# Power_1.net
KiCad netlist of a schematic drawn in Altium Designer
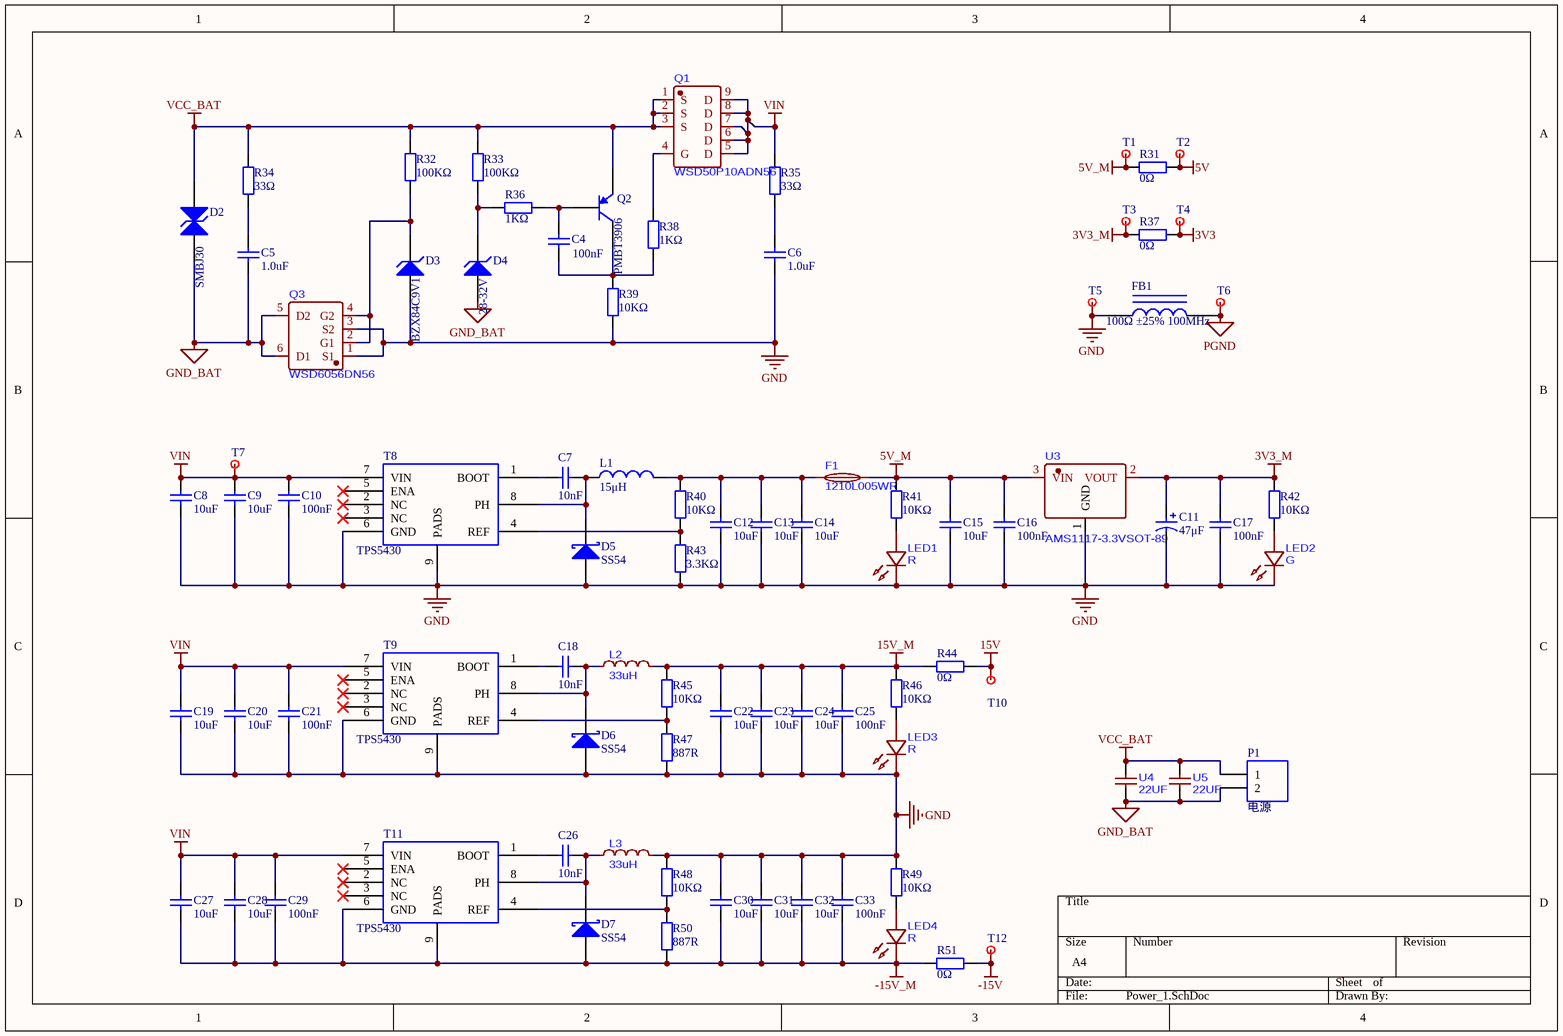
[diagram p0: Power_1.SchDoc]

(export (version "E")
  (design (tool "Eeschema 10.0.6"))
  (components
    (comp (ref "C4")
      (value "100nF")
      (footprint "0402_C")
      (description "贴片电容")
      (libsource (lib "Miscellaneous Devices LC") (part "0402 100nF (104) 10% 16V"))
    )
    (comp (ref "C5")
      (value "1.0uF")
      (footprint "0402_C")
      (description "贴片电容")
      (libsource (lib "Miscellaneous Devices LC") (part "0402 1.0uF (105) 10% 25V"))
    )
    (comp (ref "C6")
      (value "1.0uF")
      (footprint "0402_C")
      (description "贴片电容")
      (libsource (lib "Miscellaneous Devices LC") (part "0402 1.0uF (105) 10% 25V"))
    )
    (comp (ref "C7")
      (value "10nF")
      (footprint "0402_C")
      (description "贴片电容")
      (libsource (lib "Miscellaneous Devices LC") (part "0402 10nF (103) 10% 50V"))
    )
    (comp (ref "C8")
      (value "10uF")
      (footprint "1206_C")
      (description "贴片电容")
      (libsource (lib "Miscellaneous Devices LC") (part "1206 10uF (106) 10% 50V"))
    )
    (comp (ref "C9")
      (value "10uF")
      (footprint "1206_C")
      (description "贴片电容")
      (libsource (lib "Miscellaneous Devices LC") (part "1206 10uF (106) 10% 50V"))
    )
    (comp (ref "C10")
      (value "100nF")
      (footprint "0603_C")
      (description "贴片电容")
      (libsource (lib "Miscellaneous Devices LC") (part "0603 100nF (104) 10% 50V"))
    )
    (comp (ref "C11")
      (value "47μF")
      (footprint "钽电容47")
      (description "钽电容")
      (fields (field (name "PUBLISHER") "Altium Limited"))
      (libsource (lib "RM2020原理图库v1.3 (1)") (part "47μF"))
    )
    (comp (ref "C12")
      (value "10uF")
      (footprint "1206_C")
      (description "贴片电容")
      (libsource (lib "Miscellaneous Devices LC") (part "1206 10uF (106) 10% 50V"))
    )
    (comp (ref "C13")
      (value "10uF")
      (footprint "1206_C")
      (description "贴片电容")
      (libsource (lib "Miscellaneous Devices LC") (part "1206 10uF (106) 10% 50V"))
    )
    (comp (ref "C14")
      (value "10uF")
      (footprint "1206_C")
      (description "贴片电容")
      (libsource (lib "Miscellaneous Devices LC") (part "1206 10uF (106) 10% 50V"))
    )
    (comp (ref "C15")
      (value "10uF")
      (footprint "0603_C")
      (description "贴片电容")
      (libsource (lib "Miscellaneous Devices LC") (part "0603 100nF (104) 10% 50V"))
    )
    (comp (ref "C16")
      (value "100nF")
      (footprint "0603_C")
      (description "贴片电容")
      (libsource (lib "Miscellaneous Devices LC") (part "0603 100nF (104) 10% 50V"))
    )
    (comp (ref "C17")
      (value "100nF")
      (footprint "0603_C")
      (description "贴片电容")
      (libsource (lib "Miscellaneous Devices LC") (part "0603 100nF (104) 10% 50V"))
    )
    (comp (ref "C18")
      (value "10nF")
      (footprint "0402_C")
      (description "贴片电容")
      (libsource (lib "Miscellaneous Devices LC") (part "0402 10nF (103) 10% 50V"))
    )
    (comp (ref "C19")
      (value "10uF")
      (footprint "1206_C")
      (description "贴片电容")
      (libsource (lib "Miscellaneous Devices LC") (part "1206 10uF (106) 10% 50V"))
    )
    (comp (ref "C20")
      (value "10uF")
      (footprint "1206_C")
      (description "贴片电容")
      (libsource (lib "Miscellaneous Devices LC") (part "1206 10uF (106) 10% 50V"))
    )
    (comp (ref "C21")
      (value "100nF")
      (footprint "0603_C")
      (description "贴片电容")
      (libsource (lib "Miscellaneous Devices LC") (part "0603 100nF (104) 10% 50V"))
    )
    (comp (ref "C22")
      (value "10uF")
      (footprint "1206_C")
      (description "贴片电容")
      (libsource (lib "Miscellaneous Devices LC") (part "1206 10uF (106) 10% 50V"))
    )
    (comp (ref "C23")
      (value "10uF")
      (footprint "1206_C")
      (description "贴片电容")
      (libsource (lib "Miscellaneous Devices LC") (part "1206 10uF (106) 10% 50V"))
    )
    (comp (ref "C24")
      (value "10uF")
      (footprint "1206_C")
      (description "贴片电容")
      (libsource (lib "Miscellaneous Devices LC") (part "1206 10uF (106) 10% 50V"))
    )
    (comp (ref "C25")
      (value "100nF")
      (footprint "0603_C")
      (description "贴片电容")
      (libsource (lib "Miscellaneous Devices LC") (part "0603 100nF (104) 10% 50V"))
    )
    (comp (ref "C26")
      (value "10nF")
      (footprint "0402_C")
      (description "贴片电容")
      (libsource (lib "Miscellaneous Devices LC") (part "0402 10nF (103) 10% 50V"))
    )
    (comp (ref "C27")
      (value "10uF")
      (footprint "1206_C")
      (description "贴片电容")
      (libsource (lib "Miscellaneous Devices LC") (part "1206 10uF (106) 10% 50V"))
    )
    (comp (ref "C28")
      (value "10uF")
      (footprint "1206_C")
      (description "贴片电容")
      (libsource (lib "Miscellaneous Devices LC") (part "1206 10uF (106) 10% 50V"))
    )
    (comp (ref "C29")
      (value "100nF")
      (footprint "0603_C")
      (description "贴片电容")
      (libsource (lib "Miscellaneous Devices LC") (part "0603 100nF (104) 10% 50V"))
    )
    (comp (ref "C30")
      (value "10uF")
      (footprint "1206_C")
      (description "贴片电容")
      (libsource (lib "Miscellaneous Devices LC") (part "1206 10uF (106) 10% 50V"))
    )
    (comp (ref "C31")
      (value "10uF")
      (footprint "1206_C")
      (description "贴片电容")
      (libsource (lib "Miscellaneous Devices LC") (part "1206 10uF (106) 10% 50V"))
    )
    (comp (ref "C32")
      (value "10uF")
      (footprint "1206_C")
      (description "贴片电容")
      (libsource (lib "Miscellaneous Devices LC") (part "1206 10uF (106) 10% 50V"))
    )
    (comp (ref "C33")
      (value "100nF")
      (footprint "0603_C")
      (description "贴片电容")
      (libsource (lib "Miscellaneous Devices LC") (part "0603 100nF (104) 10% 50V"))
    )
    (comp (ref "D2")
      (value "SMBJ30")
      (footprint "SMB(DO-214AA)_S1")
      (description "TVS")
      (libsource (lib "Miscellaneous Devices LC") (part "SMB/DO-214AA P6SMB6.8CA"))
    )
    (comp (ref "D3")
      (value "BZX84C9V1")
      (footprint "SOD-123")
      (description "稳压二极管")
      (libsource (lib "RM2020原理图库v1.3 (1)") (part "稳压二极管"))
    )
    (comp (ref "D4")
      (value "28-32V")
      (footprint "SOD-123")
      (description "稳压二极管")
      (libsource (lib "RM2020原理图库v1.3 (1)") (part "稳压二极管"))
    )
    (comp (ref "D5")
      (value "SS54")
      (footprint "SS54")
      (description "Schottky Diode")
      (fields (field (name "PUBLISHER") "Altium Limited"))
      (libsource (lib "RM2020原理图库v1.3 (1)") (part "SS54"))
    )
    (comp (ref "D6")
      (value "SS54")
      (footprint "SS54")
      (description "Schottky Diode")
      (fields (field (name "PUBLISHER") "Altium Limited"))
      (libsource (lib "RM2020原理图库v1.3 (1)") (part "SS54"))
    )
    (comp (ref "D7")
      (value "SS54")
      (footprint "SS54")
      (description "Schottky Diode")
      (fields (field (name "PUBLISHER") "Altium Limited"))
      (libsource (lib "RM2020原理图库v1.3 (1)") (part "SS54"))
    )
    (comp (ref "F1") (value "1210L005WR") (footprint "F1210") (libsource (lib "JiangCi") (part "1210L005WR")))
    (comp (ref "FB1")
      (value "100Ω ±25% 100MHz")
      (footprint "0805_L")
      (description "贴片磁珠")
      (libsource (lib "Miscellaneous Devices LC") (part "0805 100Ω 25% 100MHz"))
    )
    (comp (ref "L1")
      (value "15μH")
      (footprint "电感")
      (description "贴片电感")
      (fields (field (name "PUBLISHER") "Altium Limited"))
      (libsource (lib "RM2020原理图库v1.3 (1)") (part "15μH"))
    )
    (comp (ref "L2")
      (value "33uH")
      (footprint "IND-SMD_L5.5-W5.0")
      (libsource (lib "JiangCi") (part "YXMAC0502-3R3M-ANF"))
    )
    (comp (ref "L3")
      (value "33uH")
      (footprint "IND-SMD_L5.5-W5.0")
      (libsource (lib "JiangCi") (part "YXMAC0502-3R3M-ANF"))
    )
    (comp (ref "LED1")
      (value "R")
      (footprint "LED0402-RD")
      (libsource (lib "JiangCi") (part "TJ-S1005CL4T5ALC3DW-A5"))
    )
    (comp (ref "LED2")
      (value "G")
      (footprint "LED0402-RD")
      (libsource (lib "JiangCi") (part "TJ-S1005CL4T5ALC3DW-A5"))
    )
    (comp (ref "LED3")
      (value "R")
      (footprint "LED0402-RD")
      (libsource (lib "JiangCi") (part "TJ-S1005CL4T5ALC3DW-A5"))
    )
    (comp (ref "LED4")
      (value "R")
      (footprint "LED0402-RD")
      (libsource (lib "JiangCi") (part "TJ-S1005CL4T5ALC3DW-A5"))
    )
    (comp (ref "P1")
      (value "电源")
      (footprint "XT30U公头")
      (description "Header, 2-Pin")
      (fields (field (name "PUBLISHER") "Altium Limited"))
      (libsource (lib "RM2020原理图库v1.3 (1)") (part "XT30公头立式"))
    )
    (comp (ref "Q1")
      (value "WSD50P10ADN56")
      (footprint "DFN-8_L5.8-W4.9-P1.27-LS6.0-BL-1")
      (libsource (lib "VeryNB_H750") (part "WSD50P10ADN56"))
    )
    (comp (ref "Q2")
      (value "PMBT3906")
      (footprint "SOT-23")
      (description "三极管")
      (libsource (lib "RM2020原理图库v1.3 (1)") (part "PNP三极管"))
    )
    (comp (ref "Q3")
      (value "WSD6056DN56")
      (footprint "DFN-8_L5.5-W5.2-P1.27-LS6.0-BL-EP2")
      (libsource (lib "VeryNB_H750") (part "WSD6056DN56"))
    )
    (comp (ref "R31")
      (value "0Ω")
      (footprint "0603_R")
      (description "贴片电阻")
      (libsource (lib "Miscellaneous Devices LC") (part "0603 0Ω (0R0) 1%"))
    )
    (comp (ref "R32")
      (value "100KΩ")
      (footprint "0402_R")
      (description "贴片电阻")
      (libsource (lib "Miscellaneous Devices LC") (part "0402 100KΩ (1003) 1%"))
    )
    (comp (ref "R33")
      (value "100KΩ")
      (footprint "0402_R")
      (description "贴片电阻")
      (libsource (lib "Miscellaneous Devices LC") (part "0402 100KΩ (1003) 1%"))
    )
    (comp (ref "R34")
      (value "33Ω")
      (footprint "0402_R")
      (description "贴片电阻")
      (libsource (lib "Miscellaneous Devices LC") (part "0402 33Ω (33R0) 1%"))
    )
    (comp (ref "R35")
      (value "33Ω")
      (footprint "0402_R")
      (description "贴片电阻")
      (libsource (lib "Miscellaneous Devices LC") (part "0402 33Ω (33R0) 1%"))
    )
    (comp (ref "R36")
      (value "1KΩ")
      (footprint "0402_R")
      (description "贴片电阻")
      (libsource (lib "") (part "0402 1KΩ (1001) 1%_1"))
    )
    (comp (ref "R37")
      (value "0Ω")
      (footprint "0603_R")
      (description "贴片电阻")
      (libsource (lib "Miscellaneous Devices LC") (part "0603 0Ω (0R0) 1%"))
    )
    (comp (ref "R38")
      (value "1KΩ")
      (footprint "0402_R")
      (description "贴片电阻")
      (libsource (lib "Miscellaneous Devices LC") (part "0402 1KΩ (1001) 1%"))
    )
    (comp (ref "R39")
      (value "10KΩ")
      (footprint "0402_R")
      (description "贴片电阻")
      (libsource (lib "") (part "0402 10KΩ (1002) 1%_1"))
    )
    (comp (ref "R40")
      (value "10KΩ")
      (footprint "0402_R")
      (description "贴片电阻")
      (libsource (lib "Miscellaneous Devices LC") (part "0402 10KΩ (1002) 1%"))
    )
    (comp (ref "R41")
      (value "10KΩ")
      (footprint "0402_R")
      (description "贴片电阻")
      (libsource (lib "Miscellaneous Devices LC") (part "0402 10KΩ (1002) 1%"))
    )
    (comp (ref "R42")
      (value "10KΩ")
      (footprint "0402_R")
      (description "贴片电阻")
      (libsource (lib "Miscellaneous Devices LC") (part "0402 10KΩ (1002) 1%"))
    )
    (comp (ref "R43")
      (value "3.3KΩ")
      (footprint "0402_R")
      (description "贴片电阻")
      (libsource (lib "Miscellaneous Devices LC") (part "0402 3.3KΩ (3301) 1%"))
    )
    (comp (ref "R44")
      (value "0Ω")
      (footprint "0603_R")
      (description "贴片电阻")
      (libsource (lib "Miscellaneous Devices LC") (part "0603 0Ω (0R0) 1%"))
    )
    (comp (ref "R45")
      (value "10KΩ")
      (footprint "0402_R")
      (description "贴片电阻")
      (libsource (lib "Miscellaneous Devices LC") (part "0402 10KΩ (1002) 1%"))
    )
    (comp (ref "R46")
      (value "10KΩ")
      (footprint "0402_R")
      (description "贴片电阻")
      (libsource (lib "Miscellaneous Devices LC") (part "0402 10KΩ (1002) 1%"))
    )
    (comp (ref "R47")
      (value "887R")
      (footprint "0402_R")
      (description "贴片电阻")
      (libsource (lib "Miscellaneous Devices LC") (part "0402 3.3KΩ (3301) 1%"))
    )
    (comp (ref "R48")
      (value "10KΩ")
      (footprint "0402_R")
      (description "贴片电阻")
      (libsource (lib "Miscellaneous Devices LC") (part "0402 10KΩ (1002) 1%"))
    )
    (comp (ref "R49")
      (value "10KΩ")
      (footprint "0402_R")
      (description "贴片电阻")
      (libsource (lib "Miscellaneous Devices LC") (part "0402 10KΩ (1002) 1%"))
    )
    (comp (ref "R50")
      (value "887R")
      (footprint "0402_R")
      (description "贴片电阻")
      (libsource (lib "Miscellaneous Devices LC") (part "0402 3.3KΩ (3301) 1%"))
    )
    (comp (ref "R51")
      (value "0Ω")
      (footprint "0603_R")
      (description "贴片电阻")
      (libsource (lib "Miscellaneous Devices LC") (part "0603 0Ω (0R0) 1%"))
    )
    (comp (ref "T1")
      (value "testpoint")
      (footprint "testpoint")
      (libsource (lib "JiangCi") (part "testpoint"))
    )
    (comp (ref "T2")
      (value "testpoint")
      (footprint "testpoint")
      (libsource (lib "JiangCi") (part "testpoint"))
    )
    (comp (ref "T3")
      (value "testpoint")
      (footprint "testpoint")
      (libsource (lib "JiangCi") (part "testpoint"))
    )
    (comp (ref "T4")
      (value "testpoint")
      (footprint "testpoint")
      (libsource (lib "JiangCi") (part "testpoint"))
    )
    (comp (ref "T5")
      (value "testpoint")
      (footprint "testpoint")
      (libsource (lib "JiangCi") (part "testpoint"))
    )
    (comp (ref "T6")
      (value "testpoint")
      (footprint "testpoint")
      (libsource (lib "JiangCi") (part "testpoint"))
    )
    (comp (ref "T7")
      (value "testpoint")
      (footprint "testpoint")
      (libsource (lib "JiangCi") (part "testpoint"))
    )
    (comp (ref "T8")
      (value "TPS5430")
      (footprint "TPS5430DDAR")
      (description "24V-5V")
      (libsource (lib "RM2020原理图库v1.3 (1)") (part "TPS5430"))
    )
    (comp (ref "T9")
      (value "TPS5430")
      (footprint "TPS5430DDAR")
      (description "24V-5V")
      (libsource (lib "RM2020原理图库v1.3 (1)") (part "TPS5430"))
    )
    (comp (ref "T10")
      (value "testpoint")
      (footprint "testpoint")
      (libsource (lib "JiangCi") (part "testpoint"))
    )
    (comp (ref "T11")
      (value "TPS5430")
      (footprint "TPS5430DDAR")
      (description "24V-5V")
      (libsource (lib "RM2020原理图库v1.3 (1)") (part "TPS5430"))
    )
    (comp (ref "T12")
      (value "testpoint")
      (footprint "testpoint")
      (libsource (lib "JiangCi") (part "testpoint"))
    )
    (comp (ref "U3")
      (value "AMS1117-3.3VSOT-89")
      (footprint "SOT-89-3_L4.5-W2.5-P1.50-LS4.2-BR")
      (libsource (lib "JiangCi") (part "AMS1117-3.3VSOT-89"))
    )
    (comp (ref "U4")
      (value "22UF")
      (footprint "C1812")
      (libsource (lib "VeryNB_H750") (part "100UF/50V-1812"))
    )
    (comp (ref "U5")
      (value "22UF")
      (footprint "C1812")
      (libsource (lib "VeryNB_H750") (part "100UF/50V-1812"))
    )
  )
  (nets
    (net (code "1") (name "-15V") (class "Default")
      (node (ref "R51") (pin "2") (pinfunction "2_2") (pintype "passive"))
      (node (ref "T12") (pin "1") (pinfunction "R_1") (pintype "passive"))
    )
    (net (code "2") (name "-15V_M") (class "Default")
      (node (ref "C27") (pin "1") (pinfunction "1_1") (pintype "passive"))
      (node (ref "C28") (pin "1") (pinfunction "1_1") (pintype "passive"))
      (node (ref "C29") (pin "1") (pinfunction "1_1") (pintype "passive"))
      (node (ref "C30") (pin "1") (pinfunction "1_1") (pintype "passive"))
      (node (ref "C31") (pin "1") (pinfunction "1_1") (pintype "passive"))
      (node (ref "C32") (pin "1") (pinfunction "1_1") (pintype "passive"))
      (node (ref "C33") (pin "1") (pinfunction "1_1") (pintype "passive"))
      (node (ref "D7") (pin "1") (pinfunction "A_1") (pintype "passive"))
      (node (ref "LED4") (pin "1") (pinfunction "K_1") (pintype "passive"))
      (node (ref "R50") (pin "1") (pinfunction "1_1") (pintype "passive"))
      (node (ref "R51") (pin "1") (pinfunction "1_1") (pintype "passive"))
      (node (ref "T11") (pin "6") (pinfunction "GND_6") (pintype "passive"))
      (node (ref "T11") (pin "9") (pinfunction "PADS_9") (pintype "passive"))
    )
    (net (code "3") (name "3V3") (class "Default")
      (node (ref "R37") (pin "2") (pinfunction "2_2") (pintype "passive"))
      (node (ref "T4") (pin "1") (pinfunction "R_1") (pintype "passive"))
    )
    (net (code "4") (name "3V3_M") (class "Default")
      (node (ref "C11") (pin "1") (pinfunction "1_1") (pintype "passive"))
      (node (ref "C17") (pin "2") (pinfunction "2_2") (pintype "passive"))
      (node (ref "R37") (pin "1") (pinfunction "1_1") (pintype "passive"))
      (node (ref "R42") (pin "2") (pinfunction "2_2") (pintype "passive"))
      (node (ref "T3") (pin "1") (pinfunction "R_1") (pintype "passive"))
      (node (ref "U3") (pin "2") (pinfunction "VOUT_2") (pintype "passive"))
    )
    (net (code "5") (name "5V") (class "Default")
      (node (ref "R31") (pin "2") (pinfunction "2_2") (pintype "passive"))
      (node (ref "T2") (pin "1") (pinfunction "R_1") (pintype "passive"))
    )
    (net (code "6") (name "5V_M") (class "Default")
      (node (ref "C15") (pin "2") (pinfunction "2_2") (pintype "passive"))
      (node (ref "C16") (pin "2") (pinfunction "2_2") (pintype "passive"))
      (node (ref "F1") (pin "2") (pinfunction "2_2") (pintype "passive"))
      (node (ref "R31") (pin "1") (pinfunction "1_1") (pintype "passive"))
      (node (ref "R41") (pin "2") (pinfunction "2_2") (pintype "passive"))
      (node (ref "T1") (pin "1") (pinfunction "R_1") (pintype "passive"))
      (node (ref "U3") (pin "3") (pinfunction "VIN_3") (pintype "passive"))
    )
    (net (code "7") (name "15V") (class "Default")
      (node (ref "R44") (pin "2") (pinfunction "2_2") (pintype "passive"))
      (node (ref "T10") (pin "1") (pinfunction "R_1") (pintype "passive"))
    )
    (net (code "8") (name "15V_M") (class "Default")
      (node (ref "C22") (pin "2") (pinfunction "2_2") (pintype "passive"))
      (node (ref "C23") (pin "2") (pinfunction "2_2") (pintype "passive"))
      (node (ref "C24") (pin "2") (pinfunction "2_2") (pintype "passive"))
      (node (ref "C25") (pin "2") (pinfunction "2_2") (pintype "passive"))
      (node (ref "L2") (pin "2") (pinfunction "2_2") (pintype "passive"))
      (node (ref "R44") (pin "1") (pinfunction "1_1") (pintype "passive"))
      (node (ref "R45") (pin "2") (pinfunction "2_2") (pintype "passive"))
      (node (ref "R46") (pin "2") (pinfunction "2_2") (pintype "passive"))
    )
    (net (code "9") (name "GND") (class "Default")
      (node (ref "C10") (pin "1") (pinfunction "1_1") (pintype "passive"))
      (node (ref "C11") (pin "2") (pinfunction "2_2") (pintype "passive"))
      (node (ref "C12") (pin "1") (pinfunction "1_1") (pintype "passive"))
      (node (ref "C13") (pin "1") (pinfunction "1_1") (pintype "passive"))
      (node (ref "C14") (pin "1") (pinfunction "1_1") (pintype "passive"))
      (node (ref "C15") (pin "1") (pinfunction "1_1") (pintype "passive"))
      (node (ref "C16") (pin "1") (pinfunction "1_1") (pintype "passive"))
      (node (ref "C17") (pin "1") (pinfunction "1_1") (pintype "passive"))
      (node (ref "C19") (pin "1") (pinfunction "1_1") (pintype "passive"))
      (node (ref "C20") (pin "1") (pinfunction "1_1") (pintype "passive"))
      (node (ref "C21") (pin "1") (pinfunction "1_1") (pintype "passive"))
      (node (ref "C22") (pin "1") (pinfunction "1_1") (pintype "passive"))
      (node (ref "C23") (pin "1") (pinfunction "1_1") (pintype "passive"))
      (node (ref "C24") (pin "1") (pinfunction "1_1") (pintype "passive"))
      (node (ref "C25") (pin "1") (pinfunction "1_1") (pintype "passive"))
      (node (ref "C30") (pin "2") (pinfunction "2_2") (pintype "passive"))
      (node (ref "C31") (pin "2") (pinfunction "2_2") (pintype "passive"))
      (node (ref "C32") (pin "2") (pinfunction "2_2") (pintype "passive"))
      (node (ref "C33") (pin "2") (pinfunction "2_2") (pintype "passive"))
      (node (ref "C6") (pin "1") (pinfunction "1_1") (pintype "passive"))
      (node (ref "C8") (pin "1") (pinfunction "1_1") (pintype "passive"))
      (node (ref "C9") (pin "1") (pinfunction "1_1") (pintype "passive"))
      (node (ref "D3") (pin "1") (pinfunction "A_1") (pintype "passive"))
      (node (ref "D5") (pin "1") (pinfunction "A_1") (pintype "passive"))
      (node (ref "D6") (pin "1") (pinfunction "A_1") (pintype "passive"))
      (node (ref "FB1") (pin "1") (pinfunction "1_1") (pintype "passive"))
      (node (ref "L3") (pin "2") (pinfunction "2_2") (pintype "passive"))
      (node (ref "LED1") (pin "1") (pinfunction "K_1") (pintype "passive"))
      (node (ref "LED2") (pin "1") (pinfunction "K_1") (pintype "passive"))
      (node (ref "LED3") (pin "1") (pinfunction "K_1") (pintype "passive"))
      (node (ref "Q3") (pin "1") (pinfunction "S1_1") (pintype "passive"))
      (node (ref "Q3") (pin "3") (pinfunction "S2_3") (pintype "passive"))
      (node (ref "R39") (pin "2") (pinfunction "2_2") (pintype "passive"))
      (node (ref "R43") (pin "1") (pinfunction "1_1") (pintype "passive"))
      (node (ref "R47") (pin "1") (pinfunction "1_1") (pintype "passive"))
      (node (ref "R48") (pin "2") (pinfunction "2_2") (pintype "passive"))
      (node (ref "R49") (pin "2") (pinfunction "2_2") (pintype "passive"))
      (node (ref "T5") (pin "1") (pinfunction "R_1") (pintype "passive"))
      (node (ref "T8") (pin "6") (pinfunction "GND_6") (pintype "passive"))
      (node (ref "T8") (pin "9") (pinfunction "PADS_9") (pintype "passive"))
      (node (ref "T9") (pin "6") (pinfunction "GND_6") (pintype "passive"))
      (node (ref "T9") (pin "9") (pinfunction "PADS_9") (pintype "passive"))
      (node (ref "U3") (pin "1") (pinfunction "GND_1") (pintype "passive"))
    )
    (net (code "10") (name "GND_BAT") (class "Default")
      (node (ref "C5") (pin "1") (pinfunction "1_1") (pintype "passive"))
      (node (ref "D2") (pin "1") (pinfunction "A_1") (pintype "passive"))
      (node (ref "D4") (pin "1") (pinfunction "A_1") (pintype "passive"))
      (node (ref "P1") (pin "2") (pinfunction "2_2") (pintype "passive"))
      (node (ref "Q3") (pin "5") (pinfunction "D2_5") (pintype "passive"))
      (node (ref "Q3") (pin "6") (pinfunction "D1_6") (pintype "passive"))
      (node (ref "U4") (pin "1") (pinfunction "1_1") (pintype "passive"))
      (node (ref "U5") (pin "1") (pinfunction "1_1") (pintype "passive"))
    )
    (net (code "11") (name "Net-(C5-Pad2)") (class "Default")
      (node (ref "C5") (pin "2") (pinfunction "2_2") (pintype "passive"))
      (node (ref "R34") (pin "1") (pinfunction "1_1") (pintype "passive"))
    )
    (net (code "12") (name "Net-(C6-Pad2)") (class "Default")
      (node (ref "C6") (pin "2") (pinfunction "2_2") (pintype "passive"))
      (node (ref "R35") (pin "1") (pinfunction "1_1") (pintype "passive"))
    )
    (net (code "13") (name "Net-(C12-Pad2)") (class "Default")
      (node (ref "C12") (pin "2") (pinfunction "2_2") (pintype "passive"))
      (node (ref "C13") (pin "2") (pinfunction "2_2") (pintype "passive"))
      (node (ref "C14") (pin "2") (pinfunction "2_2") (pintype "passive"))
      (node (ref "F1") (pin "1") (pinfunction "1_1") (pintype "passive"))
      (node (ref "L1") (pin "2") (pinfunction "2_2") (pintype "passive"))
      (node (ref "R40") (pin "2") (pinfunction "2_2") (pintype "passive"))
    )
    (net (code "14") (name "Net-(D3-K)") (class "Default")
      (node (ref "D3") (pin "2") (pinfunction "K_2") (pintype "passive"))
      (node (ref "Q3") (pin "2") (pinfunction "G1_2") (pintype "passive"))
      (node (ref "Q3") (pin "4") (pinfunction "G2_4") (pintype "passive"))
      (node (ref "R32") (pin "1") (pinfunction "1_1") (pintype "passive"))
    )
    (net (code "15") (name "Net-(D4-K)") (class "Default")
      (node (ref "D4") (pin "2") (pinfunction "K_2") (pintype "passive"))
      (node (ref "R33") (pin "1") (pinfunction "1_1") (pintype "passive"))
      (node (ref "R36") (pin "1") (pinfunction "1_1") (pintype "passive"))
    )
    (net (code "16") (name "Net-(D5-K)") (class "Default")
      (node (ref "C7") (pin "2") (pinfunction "2_2") (pintype "passive"))
      (node (ref "D5") (pin "2") (pinfunction "K_2") (pintype "passive"))
      (node (ref "L1") (pin "1") (pinfunction "1_1") (pintype "passive"))
      (node (ref "T8") (pin "8") (pinfunction "PH_8") (pintype "passive"))
    )
    (net (code "17") (name "Net-(D6-K)") (class "Default")
      (node (ref "C18") (pin "2") (pinfunction "2_2") (pintype "passive"))
      (node (ref "D6") (pin "2") (pinfunction "K_2") (pintype "passive"))
      (node (ref "L2") (pin "1") (pinfunction "1_1") (pintype "passive"))
      (node (ref "T9") (pin "8") (pinfunction "PH_8") (pintype "passive"))
    )
    (net (code "18") (name "Net-(D7-K)") (class "Default")
      (node (ref "C26") (pin "2") (pinfunction "2_2") (pintype "passive"))
      (node (ref "D7") (pin "2") (pinfunction "K_2") (pintype "passive"))
      (node (ref "L3") (pin "1") (pinfunction "1_1") (pintype "passive"))
      (node (ref "T11") (pin "8") (pinfunction "PH_8") (pintype "passive"))
    )
    (net (code "19") (name "Net-(LED1-A)") (class "Default")
      (node (ref "LED1") (pin "2") (pinfunction "A_2") (pintype "passive"))
      (node (ref "R41") (pin "1") (pinfunction "1_1") (pintype "passive"))
    )
    (net (code "20") (name "Net-(LED2-A)") (class "Default")
      (node (ref "LED2") (pin "2") (pinfunction "A_2") (pintype "passive"))
      (node (ref "R42") (pin "1") (pinfunction "1_1") (pintype "passive"))
    )
    (net (code "21") (name "Net-(LED3-A)") (class "Default")
      (node (ref "LED3") (pin "2") (pinfunction "A_2") (pintype "passive"))
      (node (ref "R46") (pin "1") (pinfunction "1_1") (pintype "passive"))
    )
    (net (code "22") (name "Net-(LED4-A)") (class "Default")
      (node (ref "LED4") (pin "2") (pinfunction "A_2") (pintype "passive"))
      (node (ref "R49") (pin "1") (pinfunction "1_1") (pintype "passive"))
    )
    (net (code "23") (name "Net-(Q1-G)") (class "Default")
      (node (ref "Q1") (pin "4") (pinfunction "G_4") (pintype "passive"))
      (node (ref "R38") (pin "2") (pinfunction "2_2") (pintype "passive"))
    )
    (net (code "24") (name "Net-(Q2-B)") (class "Default")
      (node (ref "C4") (pin "2") (pinfunction "2_2") (pintype "passive"))
      (node (ref "Q2") (pin "1") (pinfunction "B_1") (pintype "passive"))
      (node (ref "R36") (pin "2") (pinfunction "2_2") (pintype "passive"))
    )
    (net (code "25") (name "Net-(Q2-C)") (class "Default")
      (node (ref "C4") (pin "1") (pinfunction "1_1") (pintype "passive"))
      (node (ref "Q2") (pin "3") (pinfunction "C_3") (pintype "passive"))
      (node (ref "R38") (pin "1") (pinfunction "1_1") (pintype "passive"))
      (node (ref "R39") (pin "1") (pinfunction "1_1") (pintype "passive"))
    )
    (net (code "26") (name "Net-(T8-BOOT)") (class "Default")
      (node (ref "C7") (pin "1") (pinfunction "1_1") (pintype "passive"))
      (node (ref "T8") (pin "1") (pinfunction "BOOT_1") (pintype "passive"))
    )
    (net (code "27") (name "Net-(T8-REF)") (class "Default")
      (node (ref "R40") (pin "1") (pinfunction "1_1") (pintype "passive"))
      (node (ref "R43") (pin "2") (pinfunction "2_2") (pintype "passive"))
      (node (ref "T8") (pin "4") (pinfunction "REF_4") (pintype "passive"))
    )
    (net (code "28") (name "Net-(T9-BOOT)") (class "Default")
      (node (ref "C18") (pin "1") (pinfunction "1_1") (pintype "passive"))
      (node (ref "T9") (pin "1") (pinfunction "BOOT_1") (pintype "passive"))
    )
    (net (code "29") (name "Net-(T9-REF)") (class "Default")
      (node (ref "R45") (pin "1") (pinfunction "1_1") (pintype "passive"))
      (node (ref "R47") (pin "2") (pinfunction "2_2") (pintype "passive"))
      (node (ref "T9") (pin "4") (pinfunction "REF_4") (pintype "passive"))
    )
    (net (code "30") (name "Net-(T11-BOOT)") (class "Default")
      (node (ref "C26") (pin "1") (pinfunction "1_1") (pintype "passive"))
      (node (ref "T11") (pin "1") (pinfunction "BOOT_1") (pintype "passive"))
    )
    (net (code "31") (name "Net-(T11-REF)") (class "Default")
      (node (ref "R48") (pin "1") (pinfunction "1_1") (pintype "passive"))
      (node (ref "R50") (pin "2") (pinfunction "2_2") (pintype "passive"))
      (node (ref "T11") (pin "4") (pinfunction "REF_4") (pintype "passive"))
    )
    (net (code "32") (name "PGND") (class "Default")
      (node (ref "FB1") (pin "2") (pinfunction "2_2") (pintype "passive"))
      (node (ref "T6") (pin "1") (pinfunction "R_1") (pintype "passive"))
    )
    (net (code "33") (name "VCC_BAT") (class "Default")
      (node (ref "D2") (pin "2") (pinfunction "K_2") (pintype "passive"))
      (node (ref "P1") (pin "1") (pinfunction "1_1") (pintype "passive"))
      (node (ref "Q1") (pin "1") (pinfunction "S_1") (pintype "passive"))
      (node (ref "Q1") (pin "2") (pinfunction "S_2") (pintype "passive"))
      (node (ref "Q1") (pin "3") (pinfunction "S_3") (pintype "passive"))
      (node (ref "Q2") (pin "2") (pinfunction "E_2") (pintype "passive"))
      (node (ref "R32") (pin "2") (pinfunction "2_2") (pintype "passive"))
      (node (ref "R33") (pin "2") (pinfunction "2_2") (pintype "passive"))
      (node (ref "R34") (pin "2") (pinfunction "2_2") (pintype "passive"))
      (node (ref "U4") (pin "2") (pinfunction "2_2") (pintype "passive"))
      (node (ref "U5") (pin "2") (pinfunction "2_2") (pintype "passive"))
    )
    (net (code "34") (name "VIN") (class "Default")
      (node (ref "C10") (pin "2") (pinfunction "2_2") (pintype "passive"))
      (node (ref "C19") (pin "2") (pinfunction "2_2") (pintype "passive"))
      (node (ref "C20") (pin "2") (pinfunction "2_2") (pintype "passive"))
      (node (ref "C21") (pin "2") (pinfunction "2_2") (pintype "passive"))
      (node (ref "C27") (pin "2") (pinfunction "2_2") (pintype "passive"))
      (node (ref "C28") (pin "2") (pinfunction "2_2") (pintype "passive"))
      (node (ref "C29") (pin "2") (pinfunction "2_2") (pintype "passive"))
      (node (ref "C8") (pin "2") (pinfunction "2_2") (pintype "passive"))
      (node (ref "C9") (pin "2") (pinfunction "2_2") (pintype "passive"))
      (node (ref "Q1") (pin "5") (pinfunction "D_5") (pintype "passive"))
      (node (ref "Q1") (pin "6") (pinfunction "D_6") (pintype "passive"))
      (node (ref "Q1") (pin "7") (pinfunction "D_7") (pintype "passive"))
      (node (ref "Q1") (pin "8") (pinfunction "D_8") (pintype "passive"))
      (node (ref "Q1") (pin "9") (pinfunction "D_9") (pintype "passive"))
      (node (ref "R35") (pin "2") (pinfunction "2_2") (pintype "passive"))
      (node (ref "T11") (pin "7") (pinfunction "VIN_7") (pintype "passive"))
      (node (ref "T7") (pin "1") (pinfunction "R_1") (pintype "passive"))
      (node (ref "T8") (pin "7") (pinfunction "VIN_7") (pintype "passive"))
      (node (ref "T9") (pin "7") (pinfunction "VIN_7") (pintype "passive"))
    )
    (net (code "35") (name "unconnected-(T8-ENA-Pad5)") (class "Default")
      (node (ref "T8") (pin "5") (pinfunction "ENA_5") (pintype "passive+no_connect"))
    )
    (net (code "36") (name "unconnected-(T8-NC-Pad2)") (class "Default")
      (node (ref "T8") (pin "2") (pinfunction "NC_2") (pintype "passive+no_connect"))
    )
    (net (code "37") (name "unconnected-(T8-NC-Pad3)") (class "Default")
      (node (ref "T8") (pin "3") (pinfunction "NC_3") (pintype "passive+no_connect"))
    )
    (net (code "38") (name "unconnected-(T9-ENA-Pad5)") (class "Default")
      (node (ref "T9") (pin "5") (pinfunction "ENA_5") (pintype "passive+no_connect"))
    )
    (net (code "39") (name "unconnected-(T9-NC-Pad2)") (class "Default")
      (node (ref "T9") (pin "2") (pinfunction "NC_2") (pintype "passive+no_connect"))
    )
    (net (code "40") (name "unconnected-(T9-NC-Pad3)") (class "Default")
      (node (ref "T9") (pin "3") (pinfunction "NC_3") (pintype "passive+no_connect"))
    )
    (net (code "41") (name "unconnected-(T11-ENA-Pad5)") (class "Default")
      (node (ref "T11") (pin "5") (pinfunction "ENA_5") (pintype "passive+no_connect"))
    )
    (net (code "42") (name "unconnected-(T11-NC-Pad2)") (class "Default")
      (node (ref "T11") (pin "2") (pinfunction "NC_2") (pintype "passive+no_connect"))
    )
    (net (code "43") (name "unconnected-(T11-NC-Pad3)") (class "Default")
      (node (ref "T11") (pin "3") (pinfunction "NC_3") (pintype "passive+no_connect"))
    )
  )
)
